# CLOCK_GENERATOR.net
KiCad netlist of a schematic drawn in Altium Designer
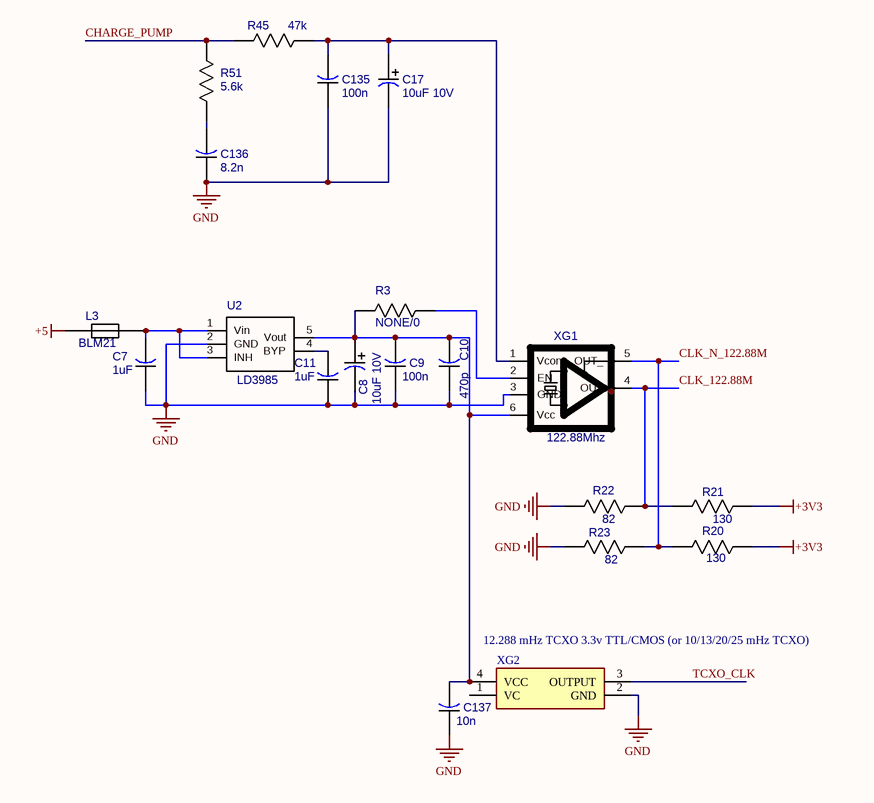
[diagram p0: CLOCK_GENERATOR.SchDoc]

(export (version "E")
  (design (tool "Eeschema 10.0.6"))
  (components
    (comp (ref "C7")
      (value "1uF")
      (footprint "CAP_0805")
      (description "CAP_0805")
      (libsource (lib "*") (part "CAP_0805"))
    )
    (comp (ref "C8")
      (value "10uF 10V")
      (footprint "CAPAE_4.3x4.3h5.4")
      (description "CAPAE_4.3x4.3h5.4")
      (libsource (lib "*") (part "CAPAE_4.3x4.3h5.4"))
    )
    (comp (ref "C9")
      (value "100n")
      (footprint "CAP_0805")
      (description "CAP_0805")
      (libsource (lib "*") (part "CAP_0805"))
    )
    (comp (ref "C10")
      (value "470p")
      (footprint "CAP_0805")
      (description "CAP_0805")
      (libsource (lib "*") (part "CAP_0805"))
    )
    (comp (ref "C11")
      (value "1uF")
      (footprint "CAP_0805")
      (description "CAP_0805")
      (libsource (lib "*") (part "CAP_0805"))
    )
    (comp (ref "C17")
      (value "10uF 10V")
      (footprint "CAPAE_4.3x4.3h5.4")
      (description "CAPAE_4.3x4.3h5.4")
      (libsource (lib "*") (part "CAPAE_4.3x4.3h5.4"))
    )
    (comp (ref "C135")
      (value "100n")
      (footprint "CAP_0805")
      (description "CAP_0805")
      (libsource (lib "*") (part "CAP_0805"))
    )
    (comp (ref "C136")
      (value "8.2n")
      (footprint "CAP_0805")
      (description "CAP_0805")
      (libsource (lib "*") (part "CAP_0805"))
    )
    (comp (ref "C137")
      (value "10n")
      (footprint "CAP_0805")
      (description "CAP_0805")
      (libsource (lib "*") (part "CAP_0805"))
    )
    (comp (ref "L3")
      (value "BLM21")
      (footprint "CAP_0805")
      (libsource (lib "MOTHERBOARD_1") (part "IND_FERRITE_BEAD"))
    )
    (comp (ref "R3")
      (value "NONE/0")
      (footprint "RES_0805")
      (description "By used crystal")
      (fields (field (name "Comment") "0/NONE"))
      (libsource (lib "*") (part "RES_0805"))
    )
    (comp (ref "R20")
      (value "130")
      (footprint "RES_0805")
      (description "RES_0805")
      (libsource (lib "*") (part "RES_0805"))
    )
    (comp (ref "R21")
      (value "130")
      (footprint "RES_0805")
      (description "RES_0805")
      (libsource (lib "*") (part "RES_0805"))
    )
    (comp (ref "R22")
      (value "82")
      (footprint "RES_0805")
      (description "RES_0805")
      (libsource (lib "*") (part "RES_0805"))
    )
    (comp (ref "R23")
      (value "82")
      (footprint "RES_0805")
      (description "RES_0805")
      (libsource (lib "*") (part "RES_0805"))
    )
    (comp (ref "R45")
      (value "47k")
      (footprint "RES_0805")
      (description "RES_0805")
      (libsource (lib "*") (part "RES_0805"))
    )
    (comp (ref "R51")
      (value "5.6k")
      (footprint "RES_0805")
      (description "RES_0805")
      (libsource (lib "*") (part "RES_0805"))
    )
    (comp (ref "U2") (value "LD3985") (footprint "LD3985") (libsource (lib "*") (part "LD3985")))
    (comp (ref "XG1")
      (value "122.88Mhz")
      (footprint "NV7050SA")
      (description "NV7050SA\r\nVG-4513CA-122.8800M-GGCT3")
      (libsource (lib "*") (part "NV7050SA"))
    )
    (comp (ref "XG2")
      (value "12.288 mHz TCXO 3.3v TTL/CMOS (or 10/13/20/25 mHz TCXO)")
      (footprint "SamacSys:581L200X2ITT")
      (description "Crystal or Oscillator")
      (fields
        (field (name "MANUFACTURER_PART_NUMBER") "581L200X2ITT")
        (field (name "MOUSER PART NUMBER") "774-581L200X2ITT")
      )
      (libsource (lib "*") (part "581L200X2ITT"))
    )
  )
  (nets
    (net (code "1") (name "+3V3") (class "Default")
      (node (ref "R20") (pin "1") (pinfunction "1_1") (pintype "passive"))
      (node (ref "R21") (pin "1") (pinfunction "1_1") (pintype "passive"))
    )
    (net (code "2") (name "+5") (class "Default")
      (node (ref "L3") (pin "1") (pinfunction "1_1") (pintype "passive"))
    )
    (net (code "3") (name "/CHARGE_PUMP") (class "Default")
      (node (ref "R45") (pin "1") (pinfunction "1_1") (pintype "passive"))
      (node (ref "R51") (pin "1") (pinfunction "1_1") (pintype "passive"))
    )
    (net (code "4") (name "/CLK_122.88M") (class "Default")
      (node (ref "R21") (pin "2") (pinfunction "2_2") (pintype "passive"))
      (node (ref "R22") (pin "1") (pinfunction "1_1") (pintype "passive"))
      (node (ref "XG1") (pin "4") (pinfunction "OUT_4") (pintype "passive"))
    )
    (net (code "5") (name "/CLK_N_122.88M") (class "Default")
      (node (ref "R20") (pin "2") (pinfunction "2_2") (pintype "passive"))
      (node (ref "R23") (pin "1") (pinfunction "1_1") (pintype "passive"))
      (node (ref "XG1") (pin "5") (pinfunction "OUT__5") (pintype "passive"))
    )
    (net (code "6") (name "/TCXO_CLK") (class "Default")
      (node (ref "XG2") (pin "3") (pinfunction "OUTPUT_3") (pintype "passive"))
    )
    (net (code "7") (name "GND") (class "Default")
      (node (ref "C10") (pin "1") (pinfunction "1_1") (pintype "passive"))
      (node (ref "C11") (pin "1") (pinfunction "1_1") (pintype "passive"))
      (node (ref "C135") (pin "1") (pinfunction "1_1") (pintype "passive"))
      (node (ref "C136") (pin "1") (pinfunction "1_1") (pintype "passive"))
      (node (ref "C137") (pin "1") (pinfunction "1_1") (pintype "passive"))
      (node (ref "C17") (pin "2") (pinfunction "MINUS_2") (pintype "passive"))
      (node (ref "C7") (pin "1") (pinfunction "1_1") (pintype "passive"))
      (node (ref "C8") (pin "2") (pinfunction "MINUS_2") (pintype "passive"))
      (node (ref "C9") (pin "1") (pinfunction "1_1") (pintype "passive"))
      (node (ref "R22") (pin "2") (pinfunction "2_2") (pintype "passive"))
      (node (ref "R23") (pin "2") (pinfunction "2_2") (pintype "passive"))
      (node (ref "U2") (pin "2") (pinfunction "GND_2") (pintype "passive"))
      (node (ref "XG1") (pin "3") (pinfunction "GND_3") (pintype "passive"))
      (node (ref "XG2") (pin "2") (pinfunction "GND_2") (pintype "passive"))
    )
    (net (code "8") (name "Net-(C8-PLUS)") (class "Default")
      (node (ref "C10") (pin "2") (pinfunction "2_2") (pintype "passive"))
      (node (ref "C137") (pin "2") (pinfunction "2_2") (pintype "passive"))
      (node (ref "C8") (pin "1") (pinfunction "PLUS_1") (pintype "passive"))
      (node (ref "C9") (pin "2") (pinfunction "2_2") (pintype "passive"))
      (node (ref "R3") (pin "1") (pinfunction "1_1") (pintype "passive"))
      (node (ref "U2") (pin "5") (pinfunction "Vout_5") (pintype "passive"))
      (node (ref "XG1") (pin "6") (pinfunction "Vcc_6") (pintype "passive"))
      (node (ref "XG2") (pin "4") (pinfunction "VCC_4") (pintype "passive"))
    )
    (net (code "9") (name "Net-(C17-PLUS)") (class "Default")
      (node (ref "C135") (pin "2") (pinfunction "2_2") (pintype "passive"))
      (node (ref "C17") (pin "1") (pinfunction "PLUS_1") (pintype "passive"))
      (node (ref "R45") (pin "2") (pinfunction "2_2") (pintype "passive"))
      (node (ref "XG1") (pin "1") (pinfunction "Vcont_1") (pintype "passive"))
    )
    (net (code "10") (name "Net-(C136-Pad2)") (class "Default")
      (node (ref "C136") (pin "2") (pinfunction "2_2") (pintype "passive"))
      (node (ref "R51") (pin "2") (pinfunction "2_2") (pintype "passive"))
    )
    (net (code "11") (name "Net-(U2-BYP)") (class "Default")
      (node (ref "C11") (pin "2") (pinfunction "2_2") (pintype "passive"))
      (node (ref "U2") (pin "4") (pinfunction "BYP_4") (pintype "passive"))
    )
    (net (code "12") (name "Net-(U2-INH)") (class "Default")
      (node (ref "C7") (pin "2") (pinfunction "2_2") (pintype "passive"))
      (node (ref "L3") (pin "2") (pinfunction "2_2") (pintype "passive"))
      (node (ref "U2") (pin "1") (pinfunction "Vin_1") (pintype "passive"))
      (node (ref "U2") (pin "3") (pinfunction "INH_3") (pintype "passive"))
    )
    (net (code "13") (name "Net-(XG1-EN)") (class "Default")
      (node (ref "R3") (pin "2") (pinfunction "2_2") (pintype "passive"))
      (node (ref "XG1") (pin "2") (pinfunction "EN_2") (pintype "passive"))
    )
    (net (code "14") (name "unconnected-(XG2-VC-Pad1)") (class "Default")
      (node (ref "XG2") (pin "1") (pinfunction "VC_1") (pintype "passive"))
    )
  )
)
